# shared_pcb.net
KiCad netlist of a schematic drawn in EAGLE
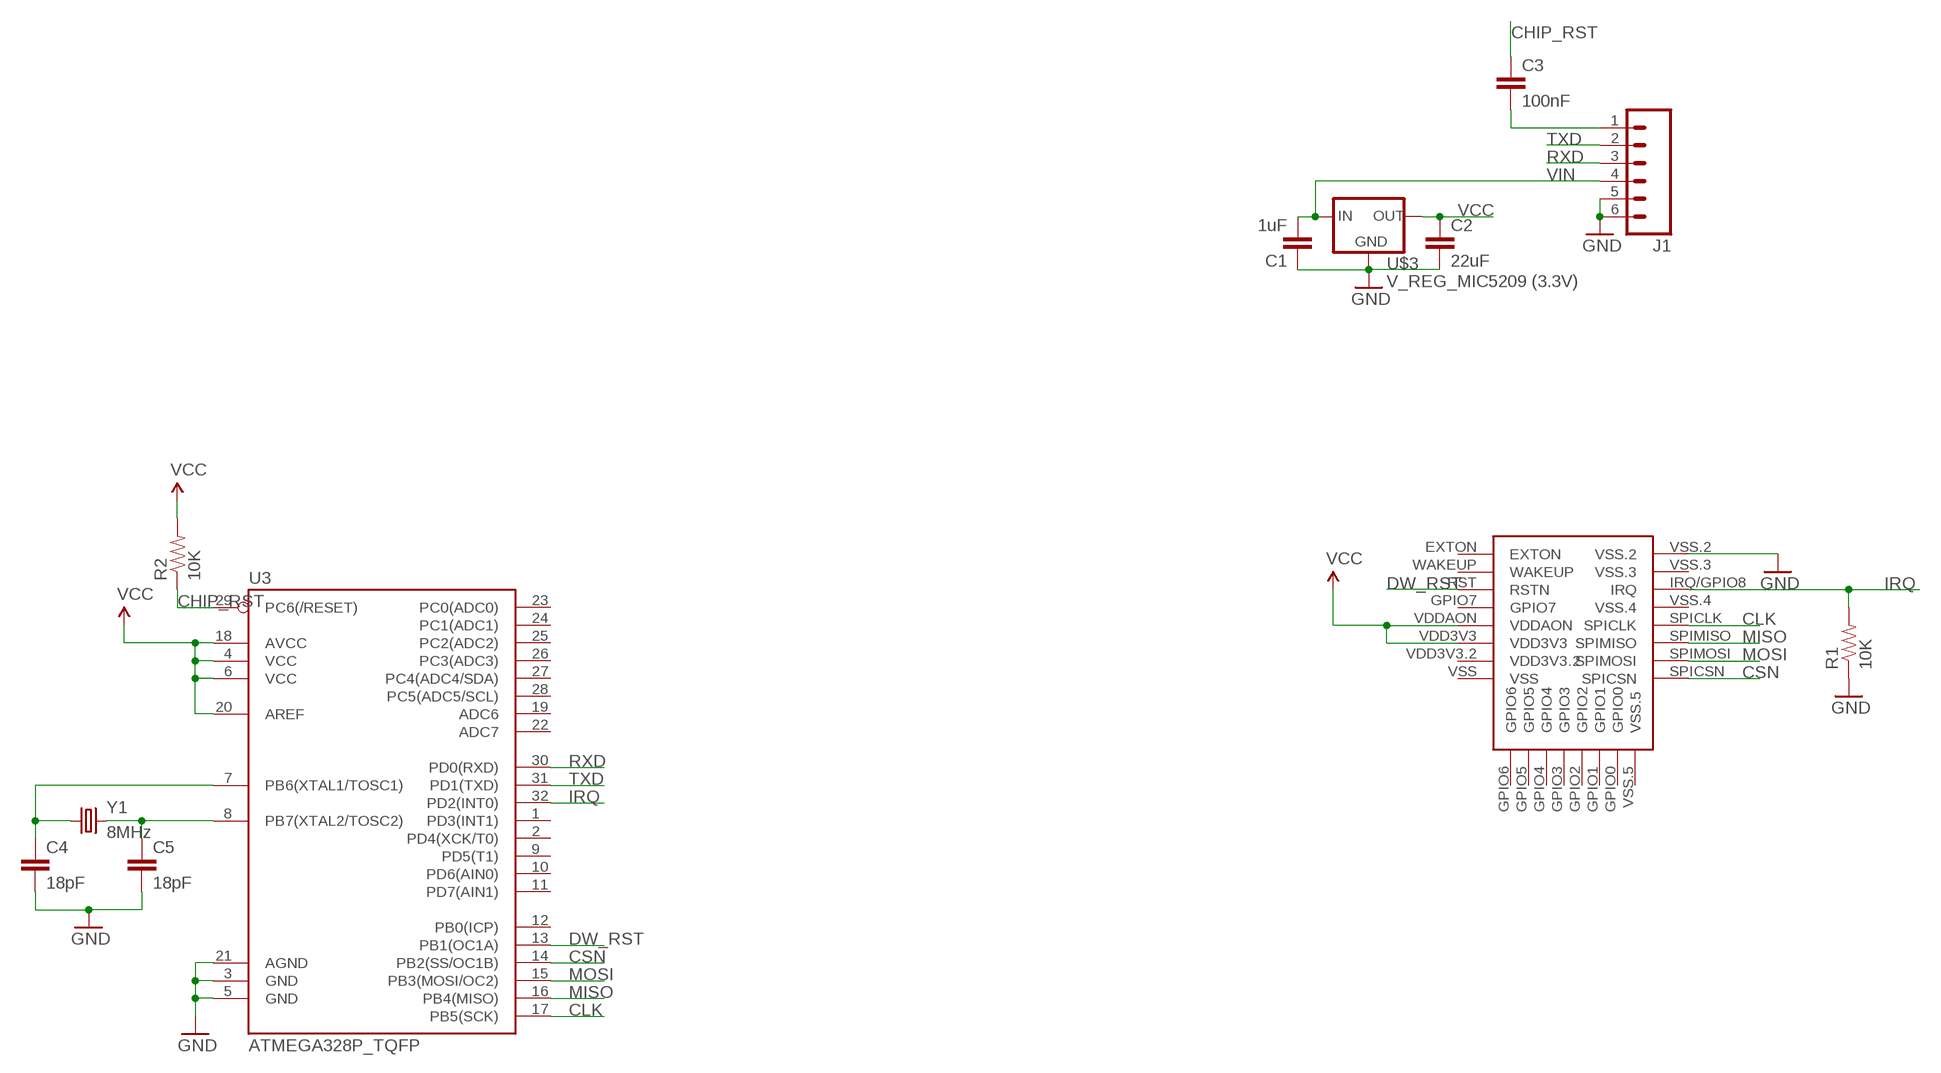
[diagram p0: schematic, sheet 1]

(export (version "E")
  (design (tool "Eeschema 10.0.6"))
  (components
    (comp (ref "C1")
      (value "1uF")
      (footprint "eagle-import:1206")
      (libsource (lib "eagle-import") (part "CAP1206"))
    )
    (comp (ref "C2")
      (value "22uF")
      (footprint "eagle-import:1206")
      (libsource (lib "eagle-import") (part "CAP1206"))
    )
    (comp (ref "C3")
      (value "100nF")
      (footprint "eagle-import:1206")
      (libsource (lib "eagle-import") (part "CAP1206"))
    )
    (comp (ref "C4")
      (value "18pF")
      (footprint "eagle-import:1206")
      (libsource (lib "eagle-import") (part "CAP1206"))
    )
    (comp (ref "C5")
      (value "18pF")
      (footprint "eagle-import:1206")
      (libsource (lib "eagle-import") (part "CAP1206"))
    )
    (comp (ref "J1")
      (value "M06LOCK")
      (footprint "eagle-import:1X06_LOCK")
      (libsource (lib "eagle-import") (part "M06LOCK"))
    )
    (comp (ref "R1")
      (value "10K")
      (footprint "eagle-import:1206")
      (libsource (lib "eagle-import") (part "RESISTOR1206"))
    )
    (comp (ref "R2")
      (value "10K")
      (footprint "eagle-import:1206")
      (libsource (lib "eagle-import") (part "RESISTOR1206"))
    )
    (comp (ref "U$1")
      (value "DWM1000")
      (footprint "eagle-import:DWM1000")
      (libsource (lib "eagle-import") (part "DWM1000"))
    )
    (comp (ref "U$3")
      (value "V_REG_MIC5209 (3.3V)")
      (footprint "eagle-import:SOT223")
      (libsource (lib "eagle-import") (part "V_REG_MIC2920"))
    )
    (comp (ref "U3")
      (value "ATMEGA328P_TQFP")
      (footprint "eagle-import:TQFP32-08")
      (libsource (lib "eagle-import") (part "ATMEGA328P_TQFP"))
    )
    (comp (ref "Y1")
      (value "8MHz")
      (footprint "eagle-import:CRYSTAL-TXC-7A")
      (libsource (lib "eagle-import") (part "CRYSTALTXC-7A"))
    )
  )
  (nets
    (net (code "1") (name "/CHIP_RST") (class "Default")
      (node (ref "C3") (pin "1") (pinfunction "1_1") (pintype "passive"))
      (node (ref "R2") (pin "1") (pinfunction "1_1") (pintype "passive"))
      (node (ref "U3") (pin "29") (pinfunction "PC6(/RESET)_29") (pintype "bidirectional"))
    )
    (net (code "2") (name "/CLK") (class "Default")
      (node (ref "U$1") (pin "SPICLK") (pinfunction "SPICLK_SPICLK") (pintype "bidirectional"))
      (node (ref "U3") (pin "17") (pinfunction "PB5(SCK)_17") (pintype "bidirectional"))
    )
    (net (code "3") (name "/CSN") (class "Default")
      (node (ref "U$1") (pin "SPICSN") (pinfunction "SPICSN_SPICSN") (pintype "bidirectional"))
      (node (ref "U3") (pin "14") (pinfunction "PB2(SS/OC1B)_14") (pintype "bidirectional"))
    )
    (net (code "4") (name "/DW_RST") (class "Default")
      (node (ref "U$1") (pin "RST") (pinfunction "RSTN_RST") (pintype "bidirectional"))
      (node (ref "U3") (pin "13") (pinfunction "PB1(OC1A)_13") (pintype "bidirectional"))
    )
    (net (code "5") (name "/IRQ") (class "Default")
      (node (ref "R1") (pin "2") (pinfunction "2_2") (pintype "passive"))
      (node (ref "U$1") (pin "IRQ/GPIO8") (pinfunction "IRQ_IRQ/GPIO8") (pintype "bidirectional"))
      (node (ref "U3") (pin "32") (pinfunction "PD2(INT0)_32") (pintype "bidirectional"))
    )
    (net (code "6") (name "/MISO") (class "Default")
      (node (ref "U$1") (pin "SPIMISO") (pinfunction "SPIMISO_SPIMISO") (pintype "bidirectional"))
      (node (ref "U3") (pin "16") (pinfunction "PB4(MISO)_16") (pintype "bidirectional"))
    )
    (net (code "7") (name "/MOSI") (class "Default")
      (node (ref "U$1") (pin "SPIMOSI") (pinfunction "SPIMOSI_SPIMOSI") (pintype "bidirectional"))
      (node (ref "U3") (pin "15") (pinfunction "PB3(MOSI/OC2)_15") (pintype "bidirectional"))
    )
    (net (code "8") (name "/RXD") (class "Default")
      (node (ref "J1") (pin "3") (pinfunction "3_3") (pintype "passive"))
      (node (ref "U3") (pin "30") (pinfunction "PD0(RXD)_30") (pintype "bidirectional"))
    )
    (net (code "9") (name "/TXD") (class "Default")
      (node (ref "J1") (pin "2") (pinfunction "2_2") (pintype "passive"))
      (node (ref "U3") (pin "31") (pinfunction "PD1(TXD)_31") (pintype "bidirectional"))
    )
    (net (code "10") (name "/VIN") (class "Default")
      (node (ref "C1") (pin "2") (pinfunction "2_2") (pintype "passive"))
      (node (ref "J1") (pin "4") (pinfunction "4_4") (pintype "passive"))
      (node (ref "U$3") (pin "1") (pinfunction "IN_1") (pintype "input"))
    )
    (net (code "11") (name "GND") (class "Default")
      (node (ref "C1") (pin "1") (pinfunction "1_1") (pintype "passive"))
      (node (ref "C2") (pin "2") (pinfunction "2_2") (pintype "passive"))
      (node (ref "C4") (pin "2") (pinfunction "2_2") (pintype "passive"))
      (node (ref "C5") (pin "2") (pinfunction "2_2") (pintype "passive"))
      (node (ref "J1") (pin "5") (pinfunction "5_5") (pintype "passive"))
      (node (ref "J1") (pin "6") (pinfunction "6_6") (pintype "passive"))
      (node (ref "R1") (pin "1") (pinfunction "1_1") (pintype "passive"))
      (node (ref "U$1") (pin "VSS.2") (pinfunction "VSS.2_VSS.2") (pintype "bidirectional"))
      (node (ref "U$3") (pin "2") (pinfunction "GND_2") (pintype "input"))
      (node (ref "U3") (pin "21") (pinfunction "AGND_21") (pintype "bidirectional"))
      (node (ref "U3") (pin "3") (pinfunction "GND_3") (pintype "bidirectional"))
      (node (ref "U3") (pin "5") (pinfunction "GND_5") (pintype "bidirectional"))
    )
    (net (code "12") (name "Net-(C3-Pad2)") (class "Default")
      (node (ref "C3") (pin "2") (pinfunction "2_2") (pintype "passive"))
      (node (ref "J1") (pin "1") (pinfunction "1_1") (pintype "passive"))
    )
    (net (code "13") (name "Net-(U3-PB6(XTAL1{slash}TOSC1))") (class "Default")
      (node (ref "C4") (pin "1") (pinfunction "1_1") (pintype "passive"))
      (node (ref "U3") (pin "7") (pinfunction "PB6(XTAL1/TOSC1)_7") (pintype "bidirectional"))
      (node (ref "Y1") (pin "P$1") (pinfunction "1_P$1") (pintype "passive"))
    )
    (net (code "14") (name "Net-(U3-PB7(XTAL2{slash}TOSC2))") (class "Default")
      (node (ref "C5") (pin "1") (pinfunction "1_1") (pintype "passive"))
      (node (ref "U3") (pin "8") (pinfunction "PB7(XTAL2/TOSC2)_8") (pintype "bidirectional"))
      (node (ref "Y1") (pin "P$2") (pinfunction "2_P$2") (pintype "passive"))
    )
    (net (code "15") (name "VCC") (class "Default")
      (node (ref "C2") (pin "1") (pinfunction "1_1") (pintype "passive"))
      (node (ref "R2") (pin "2") (pinfunction "2_2") (pintype "passive"))
      (node (ref "U$1") (pin "VDD3V3") (pinfunction "VDD3V3_VDD3V3") (pintype "bidirectional"))
      (node (ref "U$1") (pin "VDDAON") (pinfunction "VDDAON_VDDAON") (pintype "bidirectional"))
      (node (ref "U$3") (pin "3") (pinfunction "OUT_3") (pintype "passive"))
      (node (ref "U3") (pin "18") (pinfunction "AVCC_18") (pintype "bidirectional"))
      (node (ref "U3") (pin "20") (pinfunction "AREF_20") (pintype "bidirectional"))
      (node (ref "U3") (pin "4") (pinfunction "VCC_4") (pintype "bidirectional"))
      (node (ref "U3") (pin "6") (pinfunction "VCC_6") (pintype "bidirectional"))
    )
    (net (code "16") (name "unconnected-(U$1-PadEXTON)") (class "Default")
      (node (ref "U$1") (pin "EXTON") (pinfunction "EXTON_EXTON") (pintype "bidirectional"))
    )
    (net (code "17") (name "unconnected-(U$1-PadGPIO0)") (class "Default")
      (node (ref "U$1") (pin "GPIO0") (pinfunction "GPIO0_GPIO0") (pintype "bidirectional"))
    )
    (net (code "18") (name "unconnected-(U$1-PadGPIO1)") (class "Default")
      (node (ref "U$1") (pin "GPIO1") (pinfunction "GPIO1_GPIO1") (pintype "bidirectional"))
    )
    (net (code "19") (name "unconnected-(U$1-PadGPIO2)") (class "Default")
      (node (ref "U$1") (pin "GPIO2") (pinfunction "GPIO2_GPIO2") (pintype "bidirectional"))
    )
    (net (code "20") (name "unconnected-(U$1-PadGPIO3)") (class "Default")
      (node (ref "U$1") (pin "GPIO3") (pinfunction "GPIO3_GPIO3") (pintype "bidirectional"))
    )
    (net (code "21") (name "unconnected-(U$1-PadGPIO4)") (class "Default")
      (node (ref "U$1") (pin "GPIO4") (pinfunction "GPIO4_GPIO4") (pintype "bidirectional"))
    )
    (net (code "22") (name "unconnected-(U$1-PadGPIO5)") (class "Default")
      (node (ref "U$1") (pin "GPIO5") (pinfunction "GPIO5_GPIO5") (pintype "bidirectional"))
    )
    (net (code "23") (name "unconnected-(U$1-PadGPIO6)") (class "Default")
      (node (ref "U$1") (pin "GPIO6") (pinfunction "GPIO6_GPIO6") (pintype "bidirectional"))
    )
    (net (code "24") (name "unconnected-(U$1-PadGPIO7)") (class "Default")
      (node (ref "U$1") (pin "GPIO7") (pinfunction "GPIO7_GPIO7") (pintype "bidirectional"))
    )
    (net (code "25") (name "unconnected-(U$1-PadVDD3V3.2)") (class "Default")
      (node (ref "U$1") (pin "VDD3V3.2") (pinfunction "VDD3V3.2_VDD3V3.2") (pintype "bidirectional"))
    )
    (net (code "26") (name "unconnected-(U$1-PadVSS)") (class "Default")
      (node (ref "U$1") (pin "VSS") (pinfunction "VSS_VSS") (pintype "bidirectional"))
    )
    (net (code "27") (name "unconnected-(U$1-PadVSS.3)") (class "Default")
      (node (ref "U$1") (pin "VSS.3") (pinfunction "VSS.3_VSS.3") (pintype "bidirectional"))
    )
    (net (code "28") (name "unconnected-(U$1-PadVSS.4)") (class "Default")
      (node (ref "U$1") (pin "VSS.4") (pinfunction "VSS.4_VSS.4") (pintype "bidirectional"))
    )
    (net (code "29") (name "unconnected-(U$1-PadVSS.5)") (class "Default")
      (node (ref "U$1") (pin "VSS.5") (pinfunction "VSS.5_VSS.5") (pintype "bidirectional"))
    )
    (net (code "30") (name "unconnected-(U$1-PadWAKEUP)") (class "Default")
      (node (ref "U$1") (pin "WAKEUP") (pinfunction "WAKEUP_WAKEUP") (pintype "bidirectional"))
    )
    (net (code "31") (name "unconnected-(U3-ADC6-Pad19)") (class "Default")
      (node (ref "U3") (pin "19") (pinfunction "ADC6_19") (pintype "bidirectional"))
    )
    (net (code "32") (name "unconnected-(U3-ADC7-Pad22)") (class "Default")
      (node (ref "U3") (pin "22") (pinfunction "ADC7_22") (pintype "bidirectional"))
    )
    (net (code "33") (name "unconnected-(U3-PB0(ICP)-Pad12)") (class "Default")
      (node (ref "U3") (pin "12") (pinfunction "PB0(ICP)_12") (pintype "bidirectional"))
    )
    (net (code "34") (name "unconnected-(U3-PC0(ADC0)-Pad23)") (class "Default")
      (node (ref "U3") (pin "23") (pinfunction "PC0(ADC0)_23") (pintype "bidirectional"))
    )
    (net (code "35") (name "unconnected-(U3-PC1(ADC1)-Pad24)") (class "Default")
      (node (ref "U3") (pin "24") (pinfunction "PC1(ADC1)_24") (pintype "bidirectional"))
    )
    (net (code "36") (name "unconnected-(U3-PC2(ADC2)-Pad25)") (class "Default")
      (node (ref "U3") (pin "25") (pinfunction "PC2(ADC2)_25") (pintype "bidirectional"))
    )
    (net (code "37") (name "unconnected-(U3-PC3(ADC3)-Pad26)") (class "Default")
      (node (ref "U3") (pin "26") (pinfunction "PC3(ADC3)_26") (pintype "bidirectional"))
    )
    (net (code "38") (name "unconnected-(U3-PC4(ADC4{slash}SDA)-Pad27)") (class "Default")
      (node (ref "U3") (pin "27") (pinfunction "PC4(ADC4/SDA)_27") (pintype "bidirectional"))
    )
    (net (code "39") (name "unconnected-(U3-PC5(ADC5{slash}SCL)-Pad28)") (class "Default")
      (node (ref "U3") (pin "28") (pinfunction "PC5(ADC5/SCL)_28") (pintype "bidirectional"))
    )
    (net (code "40") (name "unconnected-(U3-PD3(INT1)-Pad1)") (class "Default")
      (node (ref "U3") (pin "1") (pinfunction "PD3(INT1)_1") (pintype "bidirectional"))
    )
    (net (code "41") (name "unconnected-(U3-PD4(XCK{slash}T0)-Pad2)") (class "Default")
      (node (ref "U3") (pin "2") (pinfunction "PD4(XCK/T0)_2") (pintype "bidirectional"))
    )
    (net (code "42") (name "unconnected-(U3-PD5(T1)-Pad9)") (class "Default")
      (node (ref "U3") (pin "9") (pinfunction "PD5(T1)_9") (pintype "bidirectional"))
    )
    (net (code "43") (name "unconnected-(U3-PD6(AIN0)-Pad10)") (class "Default")
      (node (ref "U3") (pin "10") (pinfunction "PD6(AIN0)_10") (pintype "bidirectional"))
    )
    (net (code "44") (name "unconnected-(U3-PD7(AIN1)-Pad11)") (class "Default")
      (node (ref "U3") (pin "11") (pinfunction "PD7(AIN1)_11") (pintype "bidirectional"))
    )
  )
)
